# MotorsController.net
KiCad netlist of a schematic drawn in Altium Designer
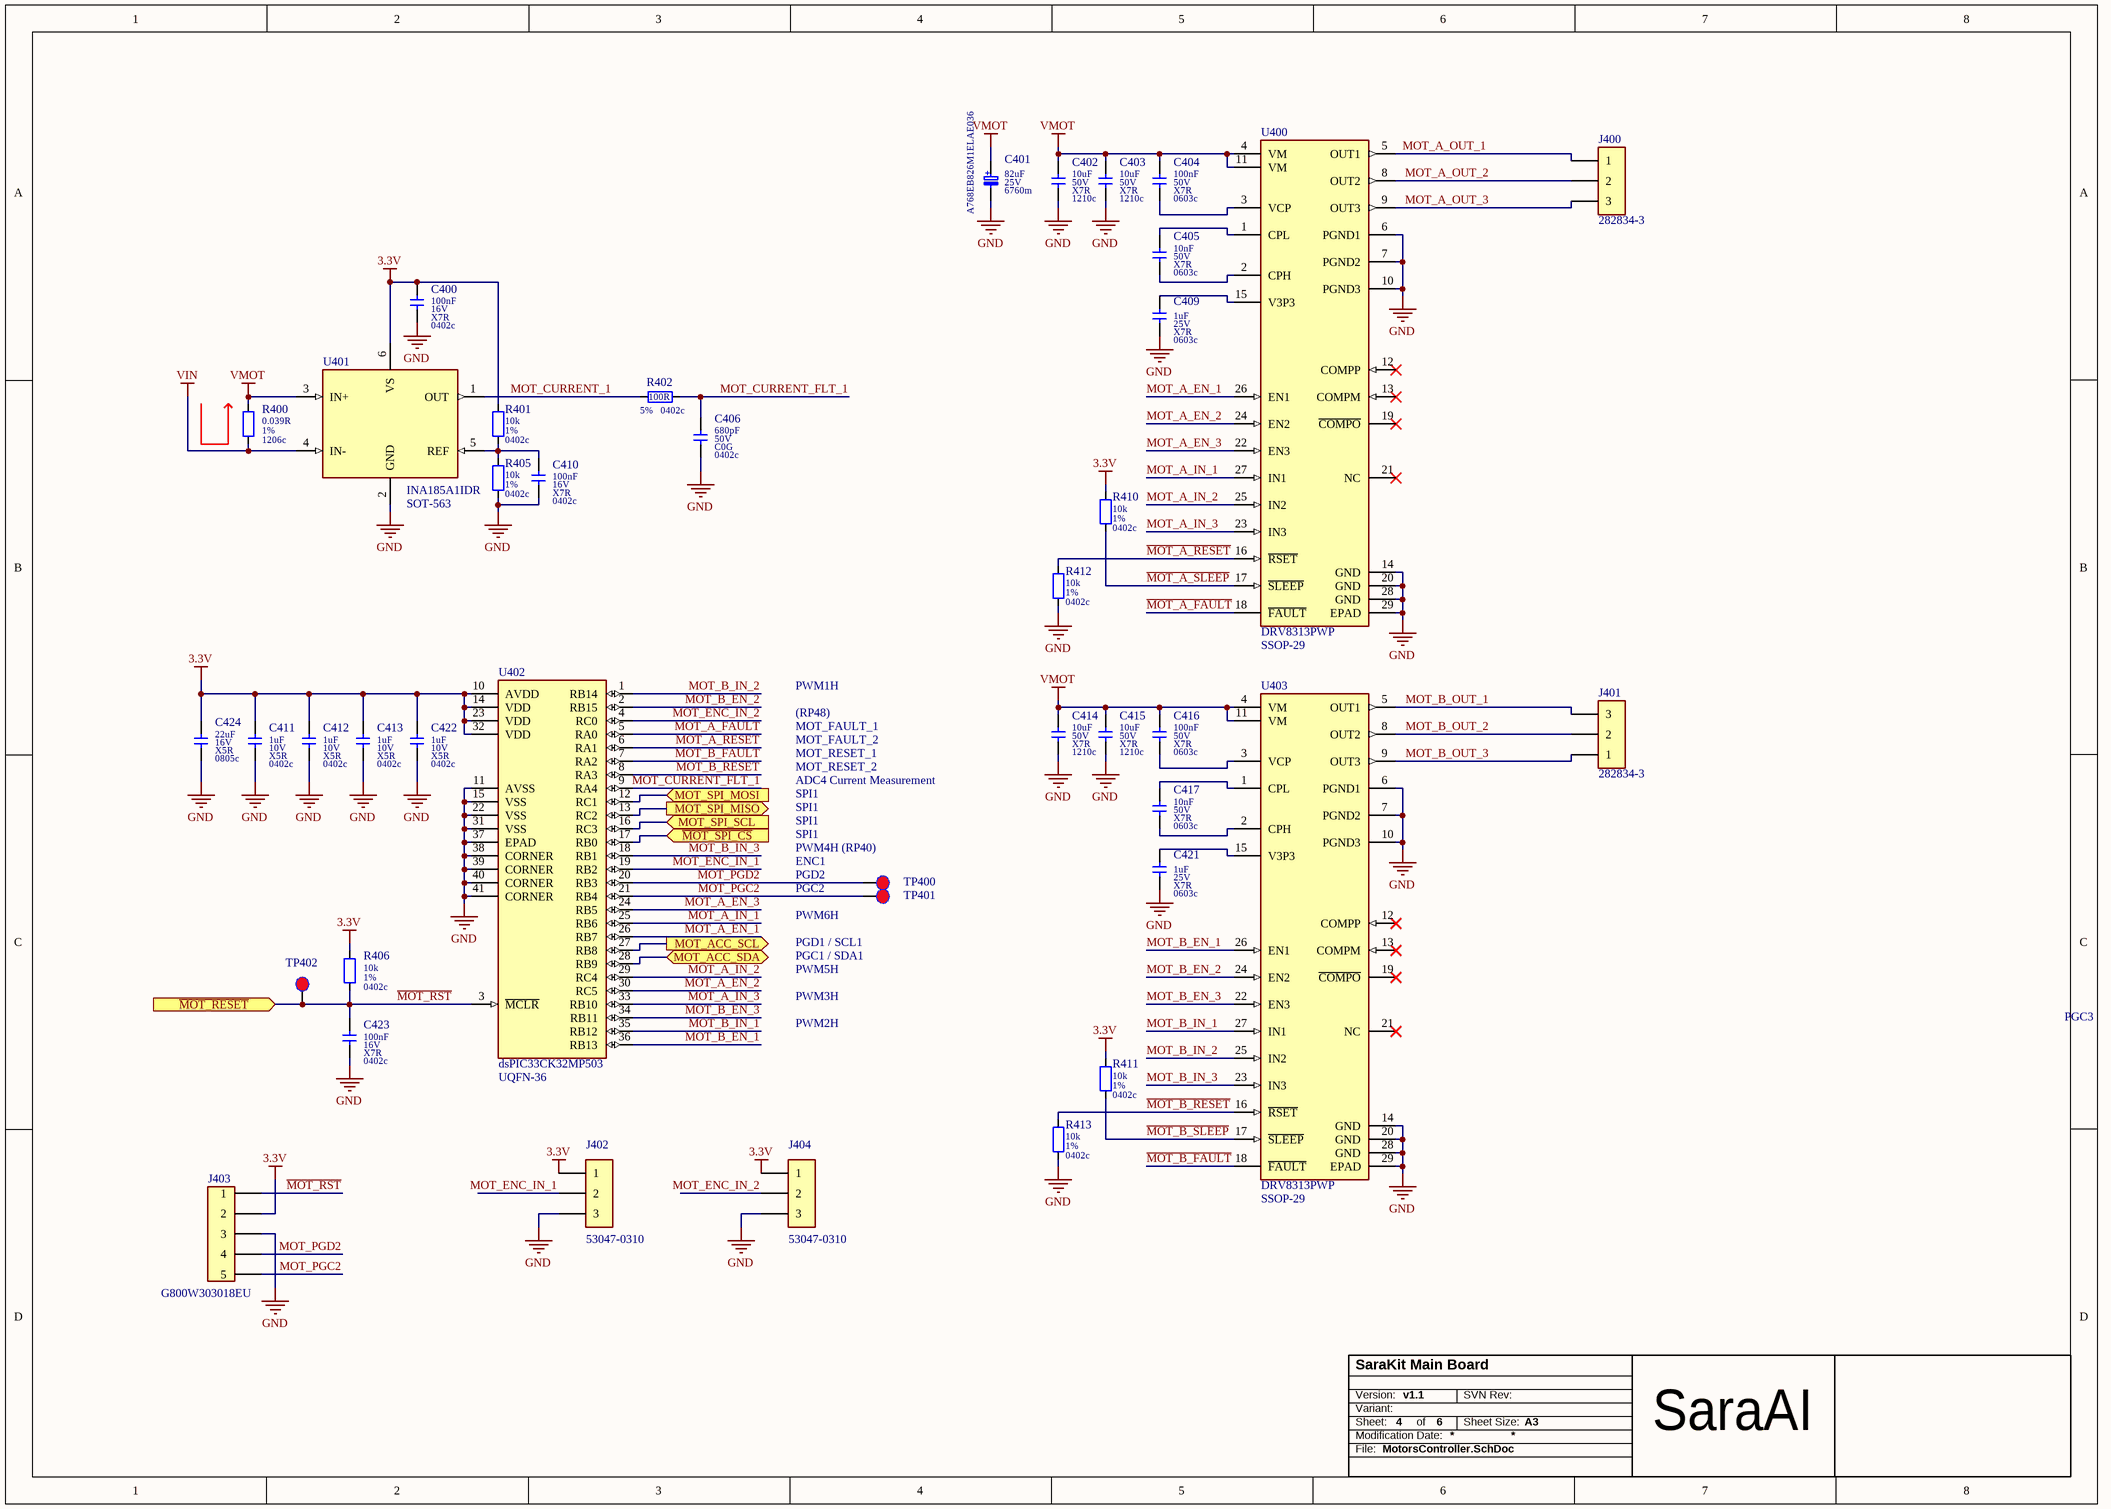
[diagram p0: MotorsController.SchDoc]

(export (version "E")
  (design (tool "Eeschema 10.0.6"))
  (components
    (comp (ref "C400")
      (value "CL05B104KO5NNNC")
      (footprint "CAPC1005X60L")
      (description "SMT 0402c 100nF 16V 10% X7R 25.8MHz 125'C")
      (fields
        (field (name "11 PARAMETER 4") "X7R")
        (field (name "07 PACKAGE") "0402c")
        (field (name "08 PARAMETER 1") "100nF")
        (field (name "09 PARAMETER 2") "16V")
      )
      (libsource (lib "MS_Altium_Lib") (part "CAPACITOR"))
    )
    (comp (ref "C401")
      (value "A768EB826M1ELAE036")
      (footprint "CAPAE660X60L")
      (description "SMT 6760m 82uF 25V 0,2 36mOhm 1.255A 125°")
      (fields
        (field (name "09 PARAMETER 2") "25V")
        (field (name "08 PARAMETER 1") "82uF")
        (field (name "02 MPN") "A768EB826M1ELAE036")
        (field (name "07 PACKAGE") "6760m")
      )
      (libsource (lib "MS_Altium_Lib") (part "CAPACITOR ELECTROLYTIC"))
    )
    (comp (ref "C402")
      (value "CL32B106KBJNNNE")
      (footprint "CAPC3225X270L")
      (description "SMT 1210c 10uF 50V 10% X7R 125°C")
      (fields
        (field (name "11 PARAMETER 4") "X7R")
        (field (name "07 PACKAGE") "1210c")
        (field (name "08 PARAMETER 1") "10uF")
        (field (name "09 PARAMETER 2") "50V")
      )
      (libsource (lib "MS_Altium_Lib") (part "CAPACITOR"))
    )
    (comp (ref "C403")
      (value "CL32B106KBJNNNE")
      (footprint "CAPC3225X270L")
      (description "SMT 1210c 10uF 50V 10% X7R 125°C")
      (fields
        (field (name "11 PARAMETER 4") "X7R")
        (field (name "07 PACKAGE") "1210c")
        (field (name "08 PARAMETER 1") "10uF")
        (field (name "09 PARAMETER 2") "50V")
      )
      (libsource (lib "MS_Altium_Lib") (part "CAPACITOR"))
    )
    (comp (ref "C404")
      (value "CL10B104KB8NNNC")
      (footprint "CAPC1608X90L")
      (description "SMT 0603c 100nF 50V 10% X7R 125'C")
      (fields
        (field (name "11 PARAMETER 4") "X7R")
        (field (name "07 PACKAGE") "0603c")
        (field (name "08 PARAMETER 1") "100nF")
        (field (name "09 PARAMETER 2") "50V")
      )
      (libsource (lib "MS_Altium_Lib") (part "CAPACITOR"))
    )
    (comp (ref "C405")
      (value "CL10B103KB8NNNC")
      (footprint "CAPC1608X90L")
      (description "SMT 0603c 10nF 50V 10% X7R 125°C")
      (fields
        (field (name "11 PARAMETER 4") "X7R")
        (field (name "07 PACKAGE") "0603c")
        (field (name "08 PARAMETER 1") "10nF")
        (field (name "09 PARAMETER 2") "50V")
      )
      (libsource (lib "MS_Altium_Lib") (part "CAPACITOR"))
    )
    (comp (ref "C406")
      (value "C0402C681J5GAC")
      (footprint "CAPC1005X60L")
      (description "SMT 0402c 680pF 50V 0,05 C0G 229MHz 125'C")
      (fields
        (field (name "11 PARAMETER 4") "C0G")
        (field (name "07 PACKAGE") "0402c")
        (field (name "08 PARAMETER 1") "680pF")
        (field (name "09 PARAMETER 2") "50V")
      )
      (libsource (lib "MS_Altium_Lib") (part "CAPACITOR"))
    )
    (comp (ref "C409")
      (value "CL10B105KA8NNNC")
      (footprint "CAPC1608X90L")
      (description "SMT 0603c 1uF 25V 10% X7R 125°C")
      (fields
        (field (name "11 PARAMETER 4") "X7R")
        (field (name "07 PACKAGE") "0603c")
        (field (name "08 PARAMETER 1") "1uF")
        (field (name "09 PARAMETER 2") "25V")
      )
      (libsource (lib "MS_Altium_Lib") (part "CAPACITOR"))
    )
    (comp (ref "C410")
      (value "CL05B104KO5NNNC")
      (footprint "CAPC1005X60L")
      (description "SMT 0402c 100nF 16V 10% X7R 25.8MHz 125'C")
      (fields
        (field (name "11 PARAMETER 4") "X7R")
        (field (name "07 PACKAGE") "0402c")
        (field (name "08 PARAMETER 1") "100nF")
        (field (name "09 PARAMETER 2") "16V")
      )
      (libsource (lib "MS_Altium_Lib") (part "CAPACITOR"))
    )
    (comp (ref "C411")
      (value "CL05A105KP5NNNC")
      (footprint "CAPC1005X60L")
      (description "SMT 0402c 1uF 10V 10% X5R 10.2MHz 85'C")
      (fields
        (field (name "11 PARAMETER 4") "X5R")
        (field (name "07 PACKAGE") "0402c")
        (field (name "08 PARAMETER 1") "1uF")
        (field (name "09 PARAMETER 2") "10V")
      )
      (libsource (lib "MS_Altium_Lib") (part "CAPACITOR"))
    )
    (comp (ref "C412")
      (value "CL05A105KP5NNNC")
      (footprint "CAPC1005X60L")
      (description "SMT 0402c 1uF 10V 10% X5R 10.2MHz 85'C")
      (fields
        (field (name "11 PARAMETER 4") "X5R")
        (field (name "07 PACKAGE") "0402c")
        (field (name "08 PARAMETER 1") "1uF")
        (field (name "09 PARAMETER 2") "10V")
      )
      (libsource (lib "MS_Altium_Lib") (part "CAPACITOR"))
    )
    (comp (ref "C413")
      (value "CL05A105KP5NNNC")
      (footprint "CAPC1005X60L")
      (description "SMT 0402c 1uF 10V 10% X5R 10.2MHz 85'C")
      (fields
        (field (name "11 PARAMETER 4") "X5R")
        (field (name "07 PACKAGE") "0402c")
        (field (name "08 PARAMETER 1") "1uF")
        (field (name "09 PARAMETER 2") "10V")
      )
      (libsource (lib "MS_Altium_Lib") (part "CAPACITOR"))
    )
    (comp (ref "C414")
      (value "CL32B106KBJNNNE")
      (footprint "CAPC3225X270L")
      (description "SMT 1210c 10uF 50V 10% X7R 125°C")
      (fields
        (field (name "11 PARAMETER 4") "X7R")
        (field (name "07 PACKAGE") "1210c")
        (field (name "08 PARAMETER 1") "10uF")
        (field (name "09 PARAMETER 2") "50V")
      )
      (libsource (lib "MS_Altium_Lib") (part "CAPACITOR"))
    )
    (comp (ref "C415")
      (value "CL32B106KBJNNNE")
      (footprint "CAPC3225X270L")
      (description "SMT 1210c 10uF 50V 10% X7R 125°C")
      (fields
        (field (name "11 PARAMETER 4") "X7R")
        (field (name "07 PACKAGE") "1210c")
        (field (name "08 PARAMETER 1") "10uF")
        (field (name "09 PARAMETER 2") "50V")
      )
      (libsource (lib "MS_Altium_Lib") (part "CAPACITOR"))
    )
    (comp (ref "C416")
      (value "CL10B104KB8NNNC")
      (footprint "CAPC1608X90L")
      (description "SMT 0603c 100nF 50V 10% X7R 125'C")
      (fields
        (field (name "11 PARAMETER 4") "X7R")
        (field (name "07 PACKAGE") "0603c")
        (field (name "08 PARAMETER 1") "100nF")
        (field (name "09 PARAMETER 2") "50V")
      )
      (libsource (lib "MS_Altium_Lib") (part "CAPACITOR"))
    )
    (comp (ref "C417")
      (value "CL10B103KB8NNNC")
      (footprint "CAPC1608X90L")
      (description "SMT 0603c 10nF 50V 10% X7R 125°C")
      (fields
        (field (name "11 PARAMETER 4") "X7R")
        (field (name "07 PACKAGE") "0603c")
        (field (name "08 PARAMETER 1") "10nF")
        (field (name "09 PARAMETER 2") "50V")
      )
      (libsource (lib "MS_Altium_Lib") (part "CAPACITOR"))
    )
    (comp (ref "C421")
      (value "CL10B105KA8NNNC")
      (footprint "CAPC1608X90L")
      (description "SMT 0603c 1uF 25V 10% X7R 125°C")
      (fields
        (field (name "11 PARAMETER 4") "X7R")
        (field (name "07 PACKAGE") "0603c")
        (field (name "08 PARAMETER 1") "1uF")
        (field (name "09 PARAMETER 2") "25V")
      )
      (libsource (lib "MS_Altium_Lib") (part "CAPACITOR"))
    )
    (comp (ref "C422")
      (value "CL05A105KP5NNNC")
      (footprint "CAPC1005X60L")
      (description "SMT 0402c 1uF 10V 10% X5R 10.2MHz 85'C")
      (fields
        (field (name "11 PARAMETER 4") "X5R")
        (field (name "07 PACKAGE") "0402c")
        (field (name "08 PARAMETER 1") "1uF")
        (field (name "09 PARAMETER 2") "10V")
      )
      (libsource (lib "MS_Altium_Lib") (part "CAPACITOR"))
    )
    (comp (ref "C423")
      (value "CL05B104KO5NNNC")
      (footprint "CAPC1005X60L")
      (description "SMT 0402c 100nF 16V 10% X7R 25.8MHz 125'C")
      (fields
        (field (name "11 PARAMETER 4") "X7R")
        (field (name "07 PACKAGE") "0402c")
        (field (name "08 PARAMETER 1") "100nF")
        (field (name "09 PARAMETER 2") "16V")
      )
      (libsource (lib "MS_Altium_Lib") (part "CAPACITOR"))
    )
    (comp (ref "C424")
      (value "CL21A226MOQNNNE")
      (footprint "CAPC2013X145L")
      (description "SMT 0805c 22uF 16V 20% X5R 1.6MHz 85'C")
      (fields
        (field (name "11 PARAMETER 4") "X5R")
        (field (name "07 PACKAGE") "0805c")
        (field (name "08 PARAMETER 1") "22uF")
        (field (name "09 PARAMETER 2") "16V")
      )
      (libsource (lib "MS_Altium_Lib") (part "CAPACITOR"))
    )
    (comp (ref "J400")
      (value "282834-3")
      (footprint "TE 282834-3")
      (description "THT 1x3 2.54mm Straight 150V 10A")
      (fields (field (name "02 MPN") "282834-3"))
      (libsource (lib "MS_Altium_Lib") (part "CONNECTOR 1X3"))
    )
    (comp (ref "J401")
      (value "282834-3")
      (footprint "TE 282834-3")
      (description "THT 1x3 2.54mm Straight 150V 10A")
      (fields (field (name "02 MPN") "282834-3"))
      (libsource (lib "") (part "CONNECTOR 1X3_1"))
    )
    (comp (ref "J402")
      (value "53047-0310")
      (footprint "MOLEX 53047-0310")
      (description "THT 1x3 1.25mm Straight 125V 1A")
      (fields (field (name "02 MPN") "53047-0310"))
      (libsource (lib "MS_Altium_Lib") (part "CONNECTOR 1X3"))
    )
    (comp (ref "J403")
      (value "G800W303018EU")
      (footprint "Goldpin 2.54 1x5")
      (description "THT 1X5 2.54mm Straight 110V 3A")
      (fields (field (name "02 MPN") "G800W303018EU"))
      (libsource (lib "MS_Altium_Lib") (part "CONNECTOR 1X5"))
    )
    (comp (ref "J404")
      (value "53047-0310")
      (footprint "MOLEX 53047-0310")
      (description "THT 1x3 1.25mm Straight 125V 1A")
      (fields (field (name "02 MPN") "53047-0310"))
      (libsource (lib "MS_Altium_Lib") (part "CONNECTOR 1X3"))
    )
    (comp (ref "R400")
      (value "ERJ-8CWFR039V")
      (footprint "RESC3216X65L")
      (description "SMT 1206c 0.039R 1% 1W 50ppm/K")
      (fields
        (field (name "07 PACKAGE") "1206c")
        (field (name "09 PARAMETER 2") "1%")
        (field (name "08 PARAMETER 1") "0.039R")
      )
      (libsource (lib "MS_Altium_Lib") (part "RESISTOR"))
    )
    (comp (ref "R401")
      (value "RC0402FR-0710KL")
      (footprint "RESC1005X40L")
      (description "SMT 0402c 10k 1% 62.5mW 100ppm/K 50V")
      (fields
        (field (name "07 PACKAGE") "0402c")
        (field (name "09 PARAMETER 2") "1%")
        (field (name "08 PARAMETER 1") "10k")
      )
      (libsource (lib "MS_Altium_Lib") (part "RESISTOR"))
    )
    (comp (ref "R402")
      (value "0402WGJ0101TCE")
      (footprint "RESC1005X40L")
      (description "SMT 0402c 100R 5% 62.5mW 200ppm/K 50V")
      (fields
        (field (name "07 PACKAGE") "0402c")
        (field (name "09 PARAMETER 2") "5%")
        (field (name "08 PARAMETER 1") "100R")
      )
      (libsource (lib "") (part "RESISTOR_1"))
    )
    (comp (ref "R405")
      (value "RC0402FR-0710KL")
      (footprint "RESC1005X40L")
      (description "SMT 0402c 10k 1% 62.5mW 100ppm/K 50V")
      (fields
        (field (name "07 PACKAGE") "0402c")
        (field (name "09 PARAMETER 2") "1%")
        (field (name "08 PARAMETER 1") "10k")
      )
      (libsource (lib "MS_Altium_Lib") (part "RESISTOR"))
    )
    (comp (ref "R406")
      (value "RC0402FR-0710KL")
      (footprint "RESC1005X40L")
      (description "SMT 0402c 10k 1% 62.5mW 100ppm/K 50V")
      (fields
        (field (name "07 PACKAGE") "0402c")
        (field (name "09 PARAMETER 2") "1%")
        (field (name "08 PARAMETER 1") "10k")
      )
      (libsource (lib "MS_Altium_Lib") (part "RESISTOR"))
    )
    (comp (ref "R410")
      (value "RC0402FR-0710KL")
      (footprint "RESC1005X40L")
      (description "SMT 0402c 10k 1% 62.5mW 100ppm/K 50V")
      (fields
        (field (name "07 PACKAGE") "0402c")
        (field (name "09 PARAMETER 2") "1%")
        (field (name "08 PARAMETER 1") "10k")
      )
      (libsource (lib "MS_Altium_Lib") (part "RESISTOR"))
    )
    (comp (ref "R411")
      (value "RC0402FR-0710KL")
      (footprint "RESC1005X40L")
      (description "SMT 0402c 10k 1% 62.5mW 100ppm/K 50V")
      (fields
        (field (name "07 PACKAGE") "0402c")
        (field (name "09 PARAMETER 2") "1%")
        (field (name "08 PARAMETER 1") "10k")
      )
      (libsource (lib "MS_Altium_Lib") (part "RESISTOR"))
    )
    (comp (ref "R412")
      (value "RC0402FR-0710KL")
      (footprint "RESC1005X40L")
      (description "SMT 0402c 10k 1% 62.5mW 100ppm/K 50V")
      (fields
        (field (name "07 PACKAGE") "0402c")
        (field (name "09 PARAMETER 2") "1%")
        (field (name "08 PARAMETER 1") "10k")
      )
      (libsource (lib "MS_Altium_Lib") (part "RESISTOR"))
    )
    (comp (ref "R413")
      (value "RC0402FR-0710KL")
      (footprint "RESC1005X40L")
      (description "SMT 0402c 10k 1% 62.5mW 100ppm/K 50V")
      (fields
        (field (name "07 PACKAGE") "0402c")
        (field (name "09 PARAMETER 2") "1%")
        (field (name "08 PARAMETER 1") "10k")
      )
      (libsource (lib "MS_Altium_Lib") (part "RESISTOR"))
    )
    (comp (ref "TP400")
      (value "TESTPAD")
      (footprint "TP 1.2mm")
      (libsource (lib "MS_Altium_Lib") (part "TESTPAD"))
    )
    (comp (ref "TP401")
      (value "TESTPAD")
      (footprint "TP 1.2mm")
      (libsource (lib "MS_Altium_Lib") (part "TESTPAD"))
    )
    (comp (ref "TP402")
      (value "TESTPAD")
      (footprint "TP 1.2mm")
      (libsource (lib "MS_Altium_Lib") (part "TESTPAD"))
    )
    (comp (ref "U400")
      (value "DRV8313PWP")
      (footprint "SOP65P640X110-HS52x31-29L")
      (description "SMT SSOP-29 Motor 60V 2.5A")
      (fields (field (name "02 MPN") "DRV8313PWP") (field (name "07 PACKAGE") "SSOP-29"))
      (libsource (lib "MS_Altium_Lib") (part "DRV8313P"))
    )
    (comp (ref "U401")
      (value "INA185A1IDR")
      (footprint "SOT50P160X120X60_6L")
      (description "SMT SOT-563 1 350kHz 2V/us")
      (fields (field (name "02 MPN") "INA185A1IDR") (field (name "07 PACKAGE") "SOT-563"))
      (libsource (lib "MS_Altium_Lib") (part "INA185A1IDRL"))
    )
    (comp (ref "U402")
      (value "dsPIC33CK32MP503")
      (footprint "QFN40P500X500X60-36_41L")
      (description "SMT UQFN-36 3-3.6V 100MHz 32kB")
      (fields (field (name "02 MPN") "dsPIC33CK32MP503") (field (name "07 PACKAGE") "UQFN-36"))
      (libsource (lib "MS_Altium_Lib") (part "dsPIC33CK32MP503-x/M5"))
    )
    (comp (ref "U403")
      (value "DRV8313PWP")
      (footprint "SOP65P640X110-HS52x31-29L")
      (description "SMT SSOP-29 Motor 60V 2.5A")
      (fields (field (name "02 MPN") "DRV8313PWP") (field (name "07 PACKAGE") "SSOP-29"))
      (libsource (lib "MS_Altium_Lib") (part "DRV8313P"))
    )
  )
  (nets
    (net (code "1") (name "/MOT_ACC_SCL") (class "Default")
      (node (ref "U402") (pin "27") (pinfunction "RB8_27") (pintype "bidirectional"))
    )
    (net (code "2") (name "/MOT_ACC_SDA") (class "Default")
      (node (ref "U402") (pin "28") (pinfunction "RB9_28") (pintype "bidirectional"))
    )
    (net (code "3") (name "/MOT_A_EN_1") (class "Default")
      (node (ref "U400") (pin "26") (pinfunction "EN1_26") (pintype "input"))
      (node (ref "U402") (pin "26") (pinfunction "RB7_26") (pintype "bidirectional"))
    )
    (net (code "4") (name "/MOT_A_EN_2") (class "Default")
      (node (ref "U400") (pin "24") (pinfunction "EN2_24") (pintype "input"))
      (node (ref "U402") (pin "30") (pinfunction "RC5_30") (pintype "bidirectional"))
    )
    (net (code "5") (name "/MOT_A_EN_3") (class "Default")
      (node (ref "U400") (pin "22") (pinfunction "EN3_22") (pintype "input"))
      (node (ref "U402") (pin "24") (pinfunction "RB5_24") (pintype "bidirectional"))
    )
    (net (code "6") (name "/MOT_A_FAULT") (class "Default")
      (node (ref "U400") (pin "18") (pinfunction "~{FAULT}_18") (pintype "open_collector"))
      (node (ref "U402") (pin "5") (pinfunction "RA0_5") (pintype "bidirectional"))
    )
    (net (code "7") (name "/MOT_A_IN_1") (class "Default")
      (node (ref "U400") (pin "27") (pinfunction "IN1_27") (pintype "input"))
      (node (ref "U402") (pin "25") (pinfunction "RB6_25") (pintype "bidirectional"))
    )
    (net (code "8") (name "/MOT_A_IN_2") (class "Default")
      (node (ref "U400") (pin "25") (pinfunction "IN2_25") (pintype "input"))
      (node (ref "U402") (pin "29") (pinfunction "RC4_29") (pintype "bidirectional"))
    )
    (net (code "9") (name "/MOT_A_IN_3") (class "Default")
      (node (ref "U400") (pin "23") (pinfunction "IN3_23") (pintype "input"))
      (node (ref "U402") (pin "33") (pinfunction "RB10_33") (pintype "bidirectional"))
    )
    (net (code "10") (name "/MOT_A_OUT_1") (class "Default")
      (node (ref "J400") (pin "1") (pinfunction "1_1") (pintype "passive"))
      (node (ref "U400") (pin "5") (pinfunction "OUT1_5") (pintype "output"))
    )
    (net (code "11") (name "/MOT_A_OUT_2") (class "Default")
      (node (ref "J400") (pin "2") (pinfunction "2_2") (pintype "passive"))
      (node (ref "U400") (pin "8") (pinfunction "OUT2_8") (pintype "output"))
    )
    (net (code "12") (name "/MOT_A_OUT_3") (class "Default")
      (node (ref "J400") (pin "3") (pinfunction "3_3") (pintype "passive"))
      (node (ref "U400") (pin "9") (pinfunction "OUT3_9") (pintype "output"))
    )
    (net (code "13") (name "/MOT_A_RESET") (class "Default")
      (node (ref "R412") (pin "2") (pinfunction "2_2") (pintype "passive"))
      (node (ref "U400") (pin "16") (pinfunction "~{RSET}_16") (pintype "input"))
      (node (ref "U402") (pin "6") (pinfunction "RA1_6") (pintype "bidirectional"))
    )
    (net (code "14") (name "/MOT_A_SLEEP") (class "Default")
      (node (ref "R410") (pin "1") (pinfunction "1_1") (pintype "passive"))
      (node (ref "U400") (pin "17") (pinfunction "~{SLEEP}_17") (pintype "input"))
    )
    (net (code "15") (name "/MOT_B_EN_1") (class "Default")
      (node (ref "U402") (pin "36") (pinfunction "RB13_36") (pintype "bidirectional"))
      (node (ref "U403") (pin "26") (pinfunction "EN1_26") (pintype "input"))
    )
    (net (code "16") (name "/MOT_B_EN_2") (class "Default")
      (node (ref "U402") (pin "2") (pinfunction "RB15_2") (pintype "bidirectional"))
      (node (ref "U403") (pin "24") (pinfunction "EN2_24") (pintype "input"))
    )
    (net (code "17") (name "/MOT_B_EN_3") (class "Default")
      (node (ref "U402") (pin "34") (pinfunction "RB11_34") (pintype "bidirectional"))
      (node (ref "U403") (pin "22") (pinfunction "EN3_22") (pintype "input"))
    )
    (net (code "18") (name "/MOT_B_FAULT") (class "Default")
      (node (ref "U402") (pin "7") (pinfunction "RA2_7") (pintype "bidirectional"))
      (node (ref "U403") (pin "18") (pinfunction "~{FAULT}_18") (pintype "open_collector"))
    )
    (net (code "19") (name "/MOT_B_IN_1") (class "Default")
      (node (ref "U402") (pin "35") (pinfunction "RB12_35") (pintype "bidirectional"))
      (node (ref "U403") (pin "27") (pinfunction "IN1_27") (pintype "input"))
    )
    (net (code "20") (name "/MOT_B_IN_2") (class "Default")
      (node (ref "U402") (pin "1") (pinfunction "RB14_1") (pintype "bidirectional"))
      (node (ref "U403") (pin "25") (pinfunction "IN2_25") (pintype "input"))
    )
    (net (code "21") (name "/MOT_B_IN_3") (class "Default")
      (node (ref "U402") (pin "18") (pinfunction "RB1_18") (pintype "bidirectional"))
      (node (ref "U403") (pin "23") (pinfunction "IN3_23") (pintype "input"))
    )
    (net (code "22") (name "/MOT_B_OUT_1") (class "Default")
      (node (ref "J401") (pin "3") (pinfunction "3_3") (pintype "passive"))
      (node (ref "U403") (pin "5") (pinfunction "OUT1_5") (pintype "output"))
    )
    (net (code "23") (name "/MOT_B_OUT_2") (class "Default")
      (node (ref "J401") (pin "2") (pinfunction "2_2") (pintype "passive"))
      (node (ref "U403") (pin "8") (pinfunction "OUT2_8") (pintype "output"))
    )
    (net (code "24") (name "/MOT_B_OUT_3") (class "Default")
      (node (ref "J401") (pin "1") (pinfunction "1_1") (pintype "passive"))
      (node (ref "U403") (pin "9") (pinfunction "OUT3_9") (pintype "output"))
    )
    (net (code "25") (name "/MOT_B_RESET") (class "Default")
      (node (ref "R413") (pin "2") (pinfunction "2_2") (pintype "passive"))
      (node (ref "U402") (pin "8") (pinfunction "RA3_8") (pintype "bidirectional"))
      (node (ref "U403") (pin "16") (pinfunction "~{RSET}_16") (pintype "input"))
    )
    (net (code "26") (name "/MOT_B_SLEEP") (class "Default")
      (node (ref "R411") (pin "1") (pinfunction "1_1") (pintype "passive"))
      (node (ref "U403") (pin "17") (pinfunction "~{SLEEP}_17") (pintype "input"))
    )
    (net (code "27") (name "/MOT_CURRENT_1") (class "Default")
      (node (ref "R402") (pin "1") (pinfunction "1_1") (pintype "passive"))
      (node (ref "U401") (pin "1") (pinfunction "OUT_1") (pintype "output"))
    )
    (net (code "28") (name "/MOT_CURRENT_FLT_1") (class "Default")
      (node (ref "C406") (pin "2") (pinfunction "2_2") (pintype "passive"))
      (node (ref "R402") (pin "2") (pinfunction "2_2") (pintype "passive"))
      (node (ref "U402") (pin "9") (pinfunction "RA4_9") (pintype "bidirectional"))
    )
    (net (code "29") (name "/MOT_ENC_IN_1") (class "Default")
      (node (ref "J402") (pin "2") (pinfunction "2_2") (pintype "passive"))
      (node (ref "U402") (pin "19") (pinfunction "RB2_19") (pintype "bidirectional"))
    )
    (net (code "30") (name "/MOT_ENC_IN_2") (class "Default")
      (node (ref "J404") (pin "2") (pinfunction "2_2") (pintype "passive"))
      (node (ref "U402") (pin "4") (pinfunction "RC0_4") (pintype "bidirectional"))
    )
    (net (code "31") (name "/MOT_PGC2") (class "Default")
      (node (ref "J403") (pin "5") (pinfunction "5_5") (pintype "passive"))
      (node (ref "TP401") (pin "1") (pinfunction "1_1") (pintype "passive"))
      (node (ref "U402") (pin "21") (pinfunction "RB4_21") (pintype "bidirectional"))
    )
    (net (code "32") (name "/MOT_PGD2") (class "Default")
      (node (ref "J403") (pin "4") (pinfunction "4_4") (pintype "passive"))
      (node (ref "TP400") (pin "1") (pinfunction "1_1") (pintype "passive"))
      (node (ref "U402") (pin "20") (pinfunction "RB3_20") (pintype "bidirectional"))
    )
    (net (code "33") (name "/MOT_RST") (class "Default")
      (node (ref "C423") (pin "2") (pinfunction "2_2") (pintype "passive"))
      (node (ref "J403") (pin "1") (pinfunction "1_1") (pintype "passive"))
      (node (ref "R406") (pin "1") (pinfunction "1_1") (pintype "passive"))
      (node (ref "TP402") (pin "1") (pinfunction "1_1") (pintype "passive"))
      (node (ref "U402") (pin "3") (pinfunction "MCLR_3") (pintype "input"))
    )
    (net (code "34") (name "/MOT_SPI_CS") (class "Default")
      (node (ref "U402") (pin "17") (pinfunction "RB0_17") (pintype "bidirectional"))
    )
    (net (code "35") (name "/MOT_SPI_MISO") (class "Default")
      (node (ref "U402") (pin "13") (pinfunction "RC2_13") (pintype "bidirectional"))
    )
    (net (code "36") (name "/MOT_SPI_MOSI") (class "Default")
      (node (ref "U402") (pin "12") (pinfunction "RC1_12") (pintype "bidirectional"))
    )
    (net (code "37") (name "/MOT_SPI_SCL") (class "Default")
      (node (ref "U402") (pin "16") (pinfunction "RC3_16") (pintype "bidirectional"))
    )
    (net (code "38") (name "3.3V") (class "Default")
      (node (ref "C400") (pin "2") (pinfunction "2_2") (pintype "passive"))
      (node (ref "C411") (pin "2") (pinfunction "2_2") (pintype "passive"))
      (node (ref "C412") (pin "2") (pinfunction "2_2") (pintype "passive"))
      (node (ref "C413") (pin "2") (pinfunction "2_2") (pintype "passive"))
      (node (ref "C422") (pin "2") (pinfunction "2_2") (pintype "passive"))
      (node (ref "C424") (pin "2") (pinfunction "2_2") (pintype "passive"))
      (node (ref "J402") (pin "1") (pinfunction "1_1") (pintype "passive"))
      (node (ref "J403") (pin "2") (pinfunction "2_2") (pintype "passive"))
      (node (ref "J404") (pin "1") (pinfunction "1_1") (pintype "passive"))
      (node (ref "R401") (pin "2") (pinfunction "2_2") (pintype "passive"))
      (node (ref "R406") (pin "2") (pinfunction "2_2") (pintype "passive"))
      (node (ref "R410") (pin "2") (pinfunction "2_2") (pintype "passive"))
      (node (ref "R411") (pin "2") (pinfunction "2_2") (pintype "passive"))
      (node (ref "U401") (pin "6") (pinfunction "VS_6") (pintype "power_in"))
      (node (ref "U402") (pin "10") (pinfunction "AVDD_10") (pintype "power_in"))
      (node (ref "U402") (pin "14") (pinfunction "VDD_14") (pintype "power_in"))
      (node (ref "U402") (pin "23") (pinfunction "VDD_23") (pintype "power_in"))
      (node (ref "U402") (pin "32") (pinfunction "VDD_32") (pintype "power_in"))
    )
    (net (code "39") (name "GND") (class "Default")
      (node (ref "C400") (pin "1") (pinfunction "1_1") (pintype "passive"))
      (node (ref "C401") (pin "2") (pinfunction "2_2") (pintype "passive"))
      (node (ref "C402") (pin "1") (pinfunction "1_1") (pintype "passive"))
      (node (ref "C403") (pin "1") (pinfunction "1_1") (pintype "passive"))
      (node (ref "C406") (pin "1") (pinfunction "1_1") (pintype "passive"))
      (node (ref "C409") (pin "1") (pinfunction "1_1") (pintype "passive"))
      (node (ref "C410") (pin "1") (pinfunction "1_1") (pintype "passive"))
      (node (ref "C411") (pin "1") (pinfunction "1_1") (pintype "passive"))
      (node (ref "C412") (pin "1") (pinfunction "1_1") (pintype "passive"))
      (node (ref "C413") (pin "1") (pinfunction "1_1") (pintype "passive"))
      (node (ref "C414") (pin "1") (pinfunction "1_1") (pintype "passive"))
      (node (ref "C415") (pin "1") (pinfunction "1_1") (pintype "passive"))
      (node (ref "C421") (pin "1") (pinfunction "1_1") (pintype "passive"))
      (node (ref "C422") (pin "1") (pinfunction "1_1") (pintype "passive"))
      (node (ref "C423") (pin "1") (pinfunction "1_1") (pintype "passive"))
      (node (ref "C424") (pin "1") (pinfunction "1_1") (pintype "passive"))
      (node (ref "J402") (pin "3") (pinfunction "3_3") (pintype "passive"))
      (node (ref "J403") (pin "3") (pinfunction "3_3") (pintype "passive"))
      (node (ref "J404") (pin "3") (pinfunction "3_3") (pintype "passive"))
      (node (ref "R405") (pin "1") (pinfunction "1_1") (pintype "passive"))
      (node (ref "R412") (pin "1") (pinfunction "1_1") (pintype "passive"))
      (node (ref "R413") (pin "1") (pinfunction "1_1") (pintype "passive"))
      (node (ref "U400") (pin "10") (pinfunction "PGND3_10") (pintype "power_in"))
      (node (ref "U400") (pin "14") (pinfunction "GND_14") (pintype "power_in"))
      (node (ref "U400") (pin "20") (pinfunction "GND_20") (pintype "power_in"))
      (node (ref "U400") (pin "28") (pinfunction "GND_28") (pintype "power_in"))
      (node (ref "U400") (pin "29") (pinfunction "EPAD_29") (pintype "power_in"))
      (node (ref "U400") (pin "6") (pinfunction "PGND1_6") (pintype "power_in"))
      (node (ref "U400") (pin "7") (pinfunction "PGND2_7") (pintype "power_in"))
      (node (ref "U401") (pin "2") (pinfunction "GND_2") (pintype "power_in"))
      (node (ref "U402") (pin "11") (pinfunction "AVSS_11") (pintype "power_in"))
      (node (ref "U402") (pin "15") (pinfunction "VSS_15") (pintype "power_in"))
      (node (ref "U402") (pin "22") (pinfunction "VSS_22") (pintype "power_in"))
      (node (ref "U402") (pin "31") (pinfunction "VSS_31") (pintype "power_in"))
      (node (ref "U402") (pin "37") (pinfunction "EPAD_37") (pintype "power_in"))
      (node (ref "U402") (pin "38") (pinfunction "CORNER_38") (pintype "power_in"))
      (node (ref "U402") (pin "39") (pinfunction "CORNER_39") (pintype "power_in"))
      (node (ref "U402") (pin "40") (pinfunction "CORNER_40") (pintype "power_in"))
      (node (ref "U402") (pin "41") (pinfunction "CORNER_41") (pintype "power_in"))
      (node (ref "U403") (pin "10") (pinfunction "PGND3_10") (pintype "power_in"))
      (node (ref "U403") (pin "14") (pinfunction "GND_14") (pintype "power_in"))
      (node (ref "U403") (pin "20") (pinfunction "GND_20") (pintype "power_in"))
      (node (ref "U403") (pin "28") (pinfunction "GND_28") (pintype "power_in"))
      (node (ref "U403") (pin "29") (pinfunction "EPAD_29") (pintype "power_in"))
      (node (ref "U403") (pin "6") (pinfunction "PGND1_6") (pintype "power_in"))
      (node (ref "U403") (pin "7") (pinfunction "PGND2_7") (pintype "power_in"))
    )
    (net (code "40") (name "Net-(U400-CPH)") (class "Default")
      (node (ref "C405") (pin "1") (pinfunction "1_1") (pintype "passive"))
      (node (ref "U400") (pin "2") (pinfunction "CPH_2") (pintype "power_in"))
    )
    (net (code "41") (name "Net-(U400-CPL)") (class "Default")
      (node (ref "C405") (pin "2") (pinfunction "2_2") (pintype "passive"))
      (node (ref "U400") (pin "1") (pinfunction "CPL_1") (pintype "power_in"))
    )
    (net (code "42") (name "Net-(U400-V3P3)") (class "Default")
      (node (ref "C409") (pin "2") (pinfunction "2_2") (pintype "passive"))
      (node (ref "U400") (pin "15") (pinfunction "V3P3_15") (pintype "power_in"))
    )
    (net (code "43") (name "Net-(U400-VCP)") (class "Default")
      (node (ref "C404") (pin "1") (pinfunction "1_1") (pintype "passive"))
      (node (ref "U400") (pin "3") (pinfunction "VCP_3") (pintype "power_in"))
    )
    (net (code "44") (name "Net-(U401-REF)") (class "Default")
      (node (ref "C410") (pin "2") (pinfunction "2_2") (pintype "passive"))
      (node (ref "R401") (pin "1") (pinfunction "1_1") (pintype "passive"))
      (node (ref "R405") (pin "2") (pinfunction "2_2") (pintype "passive"))
      (node (ref "U401") (pin "5") (pinfunction "REF_5") (pintype "input"))
    )
    (net (code "45") (name "Net-(U403-CPH)") (class "Default")
      (node (ref "C417") (pin "1") (pinfunction "1_1") (pintype "passive"))
      (node (ref "U403") (pin "2") (pinfunction "CPH_2") (pintype "power_in"))
    )
    (net (code "46") (name "Net-(U403-CPL)") (class "Default")
      (node (ref "C417") (pin "2") (pinfunction "2_2") (pintype "passive"))
      (node (ref "U403") (pin "1") (pinfunction "CPL_1") (pintype "power_in"))
    )
    (net (code "47") (name "Net-(U403-V3P3)") (class "Default")
      (node (ref "C421") (pin "2") (pinfunction "2_2") (pintype "passive"))
      (node (ref "U403") (pin "15") (pinfunction "V3P3_15") (pintype "power_in"))
    )
    (net (code "48") (name "Net-(U403-VCP)") (class "Default")
      (node (ref "C416") (pin "1") (pinfunction "1_1") (pintype "passive"))
      (node (ref "U403") (pin "3") (pinfunction "VCP_3") (pintype "power_in"))
    )
    (net (code "49") (name "VIN") (class "Default")
      (node (ref "R400") (pin "1") (pinfunction "1_1") (pintype "passive"))
      (node (ref "U401") (pin "4") (pinfunction "IN-_4") (pintype "input"))
    )
    (net (code "50") (name "VMOT") (class "Default")
      (node (ref "C401") (pin "1") (pinfunction "1_1") (pintype "passive"))
      (node (ref "C402") (pin "2") (pinfunction "2_2") (pintype "passive"))
      (node (ref "C403") (pin "2") (pinfunction "2_2") (pintype "passive"))
      (node (ref "C404") (pin "2") (pinfunction "2_2") (pintype "passive"))
      (node (ref "C414") (pin "2") (pinfunction "2_2") (pintype "passive"))
      (node (ref "C415") (pin "2") (pinfunction "2_2") (pintype "passive"))
      (node (ref "C416") (pin "2") (pinfunction "2_2") (pintype "passive"))
      (node (ref "R400") (pin "2") (pinfunction "2_2") (pintype "passive"))
      (node (ref "U400") (pin "11") (pinfunction "VM_11") (pintype "power_in"))
      (node (ref "U400") (pin "4") (pinfunction "VM_4") (pintype "power_in"))
      (node (ref "U401") (pin "3") (pinfunction "IN+_3") (pintype "input"))
      (node (ref "U403") (pin "11") (pinfunction "VM_11") (pintype "power_in"))
      (node (ref "U403") (pin "4") (pinfunction "VM_4") (pintype "power_in"))
    )
    (net (code "51") (name "unconnected-(U400-COMPM-Pad13)") (class "Default")
      (node (ref "U400") (pin "13") (pinfunction "COMPM_13") (pintype "input+no_connect"))
    )
    (net (code "52") (name "unconnected-(U400-COMPP-Pad12)") (class "Default")
      (node (ref "U400") (pin "12") (pinfunction "COMPP_12") (pintype "input+no_connect"))
    )
    (net (code "53") (name "unconnected-(U400-NC-Pad21)") (class "Default")
      (node (ref "U400") (pin "21") (pinfunction "NC_21") (pintype "passive+no_connect"))
    )
    (net (code "54") (name "unconnected-(U400-~{COMPO}-Pad19)") (class "Default")
      (node (ref "U400") (pin "19") (pinfunction "~{COMPO}_19") (pintype "open_collector+no_connect"))
    )
    (net (code "55") (name "unconnected-(U403-COMPM-Pad13)") (class "Default")
      (node (ref "U403") (pin "13") (pinfunction "COMPM_13") (pintype "input+no_connect"))
    )
    (net (code "56") (name "unconnected-(U403-COMPP-Pad12)") (class "Default")
      (node (ref "U403") (pin "12") (pinfunction "COMPP_12") (pintype "input+no_connect"))
    )
    (net (code "57") (name "unconnected-(U403-NC-Pad21)") (class "Default")
      (node (ref "U403") (pin "21") (pinfunction "NC_21") (pintype "passive+no_connect"))
    )
    (net (code "58") (name "unconnected-(U403-~{COMPO}-Pad19)") (class "Default")
      (node (ref "U403") (pin "19") (pinfunction "~{COMPO}_19") (pintype "open_collector+no_connect"))
    )
  )
)
